# PCB_3U_DAC.net
KiCad netlist of a schematic drawn in Altium Designer
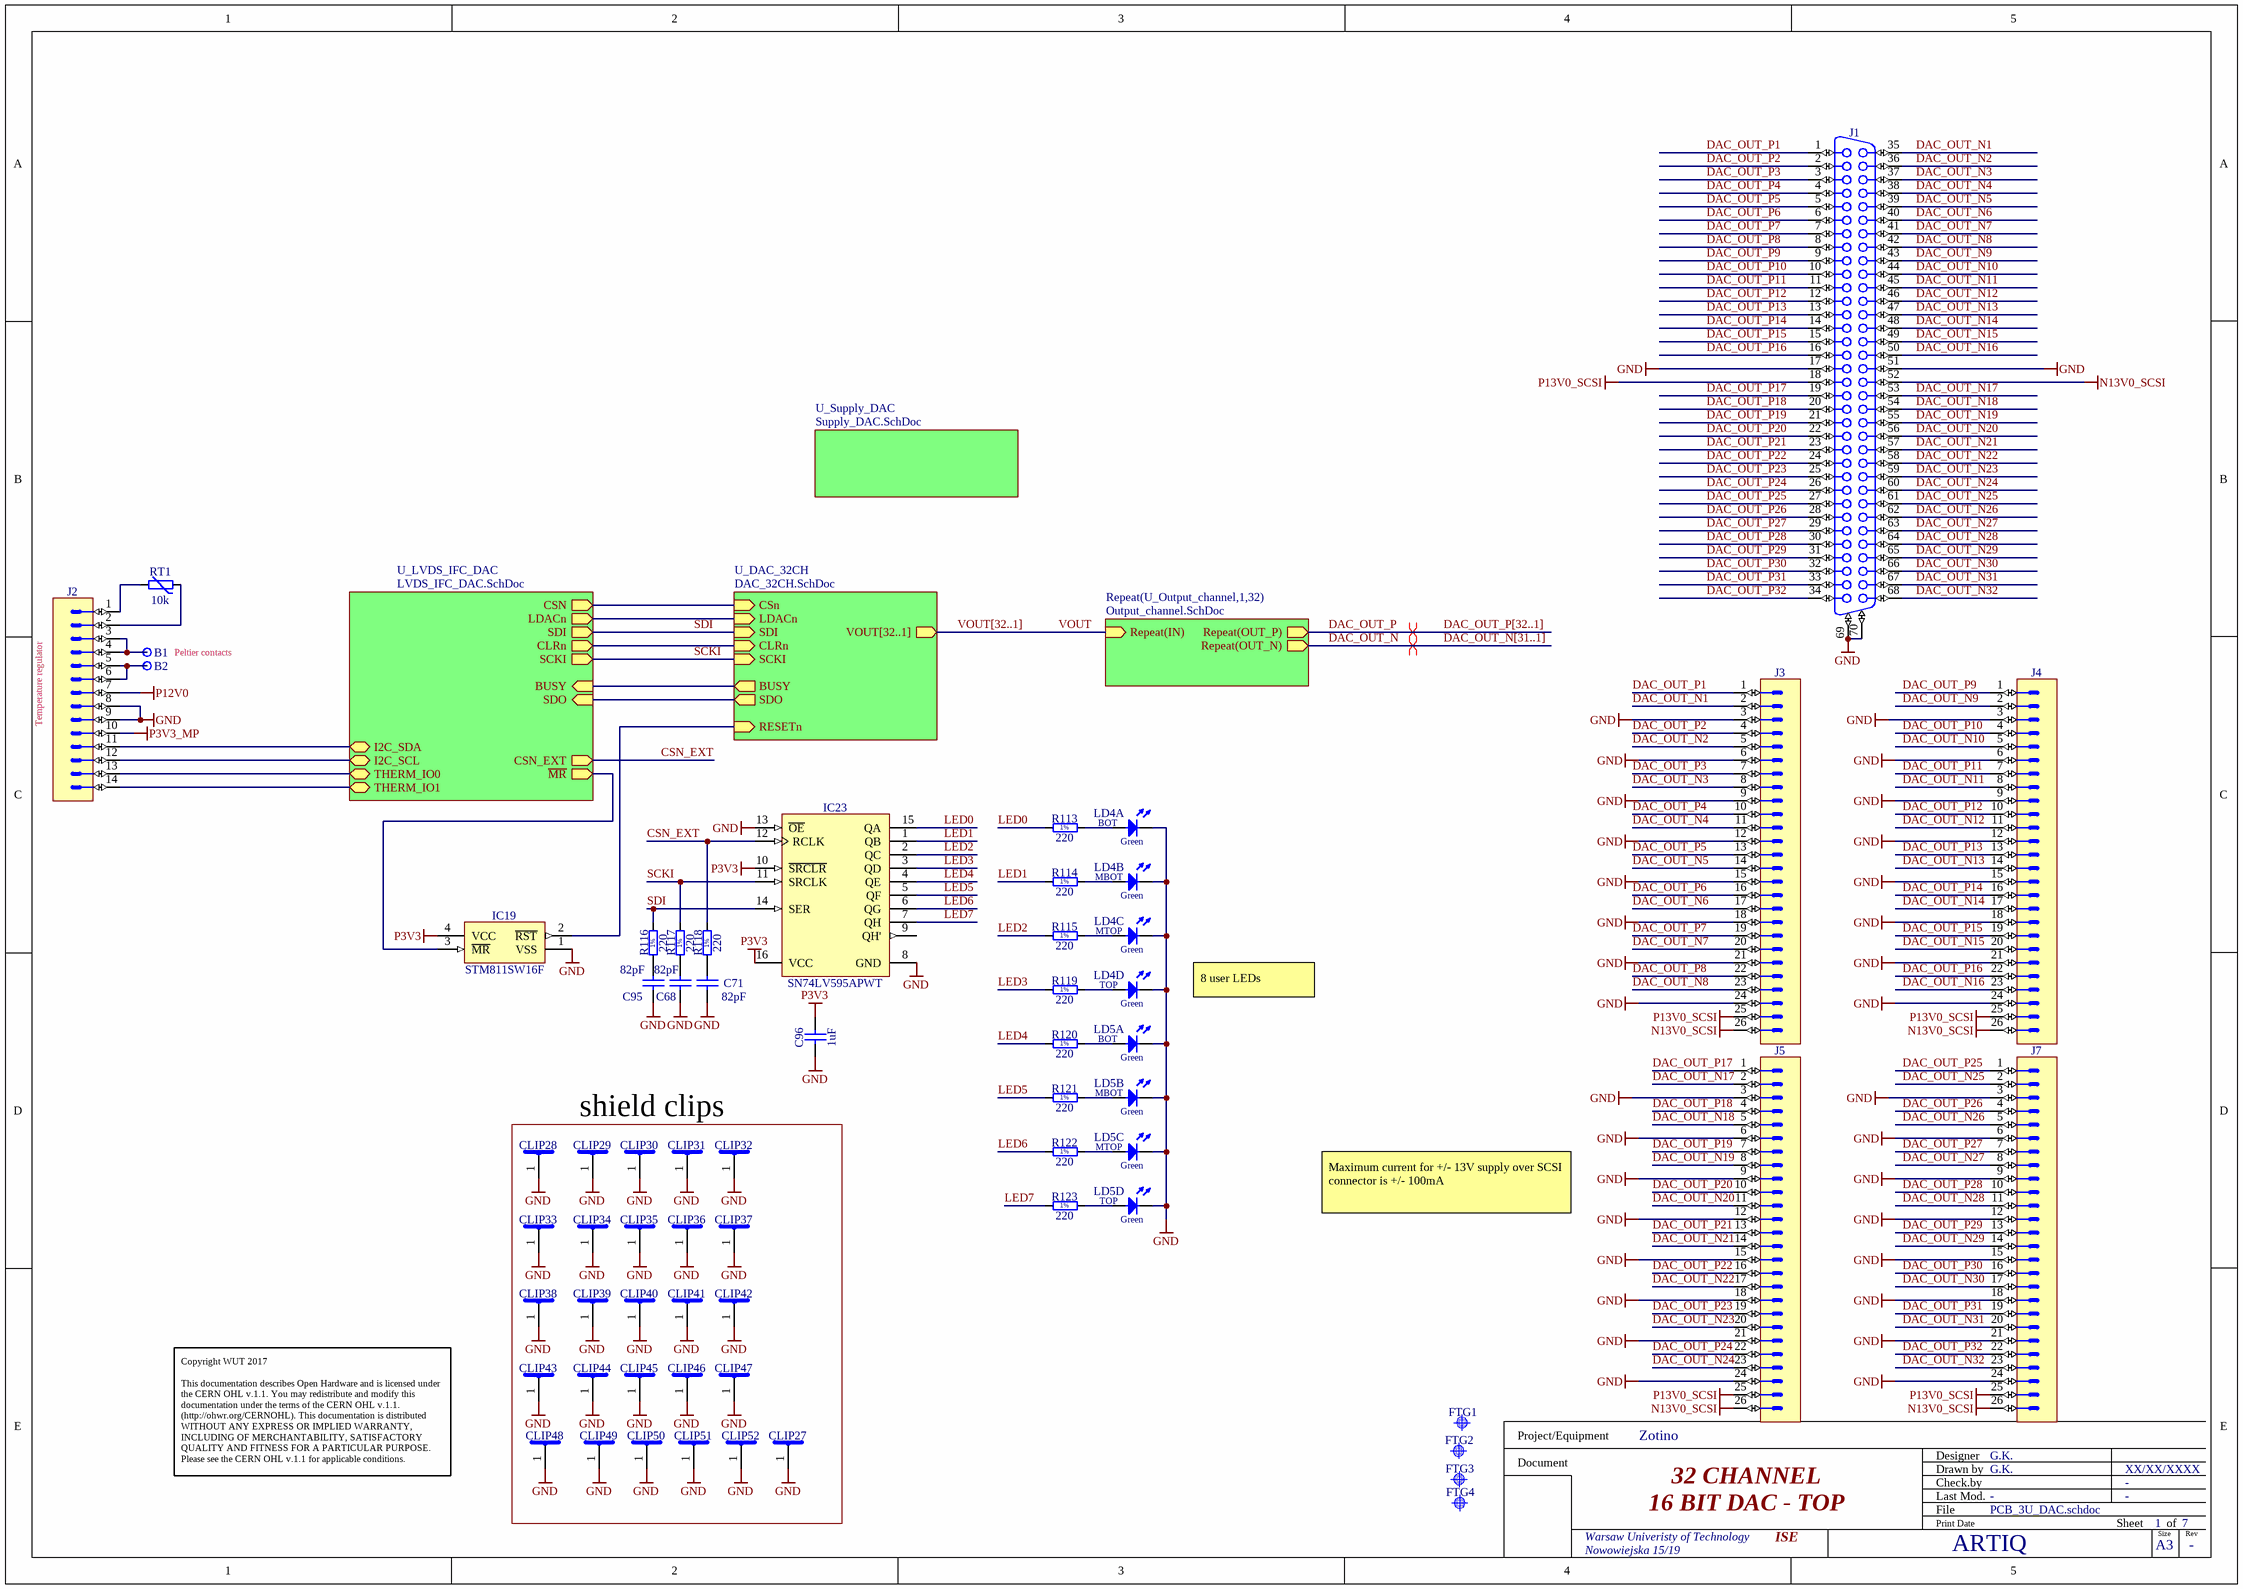
[diagram p0: PCB_3U_DAC.schdoc]

(export (version "E")
  (design (tool "Eeschema 10.0.6"))
  (components
    (comp (ref "B1")
      (value "Plated Hole")
      (footprint "c140h90")
      (description "Single Terminal Socket")
      (fields (field (name "PART NUMBER") "PLATED_HOLE0.9_PAD1.4") (field (name "AUTHOR") "CERN DEM JLC"))
      (libsource (lib "Eletro-mechanical") (part "Single Terminal Socket"))
    )
    (comp (ref "B2")
      (value "Plated Hole")
      (footprint "c140h90")
      (description "Single Terminal Socket")
      (fields (field (name "PART NUMBER") "PLATED_HOLE0.9_PAD1.4") (field (name "AUTHOR") "CERN DEM JLC"))
      (libsource (lib "Eletro-mechanical") (part "Single Terminal Socket"))
    )
    (comp (ref "C68")
      (value "82pF")
      (footprint "CAPC1608X87N")
      (description "Non-polarised capacitor")
      (fields
        (field (name "PART NUMBER") "CC0603_82PF_50V_5%_NP0")
        (field (name "VOLTAGE") "50V")
        (field (name "AUTHOR") "CERN DEM JLC")
      )
      (libsource (lib "Capacitors") (part "Capacitor - non polarized"))
    )
    (comp (ref "C71")
      (value "82pF")
      (footprint "CAPC1608X87N")
      (description "Non-polarised capacitor")
      (fields
        (field (name "PART NUMBER") "CC0603_82PF_50V_5%_NP0")
        (field (name "VOLTAGE") "50V")
        (field (name "AUTHOR") "CERN DEM JLC")
      )
      (libsource (lib "Capacitors") (part "Capacitor - non polarized"))
    )
    (comp (ref "C95")
      (value "82pF")
      (footprint "CAPC1608X87N")
      (description "Non-polarised capacitor")
      (fields
        (field (name "PART NUMBER") "CC0603_82PF_50V_5%_NP0")
        (field (name "VOLTAGE") "50V")
        (field (name "AUTHOR") "CERN DEM JLC")
      )
      (libsource (lib "Capacitors") (part "Capacitor - non polarized"))
    )
    (comp (ref "C96")
      (value "1uF")
      (footprint "CAPC1608X87N")
      (description "Non-polarised capacitor")
      (fields
        (field (name "PART NUMBER") "CC0603_1UF_25V_10%_X7R")
        (field (name "VOLTAGE") "25V")
        (field (name "AUTHOR") "CERN DEM JLC")
      )
      (libsource (lib "Capacitors") (part "Capacitor - non polarized"))
    )
    (comp (ref "CLIP27")
      (value "S1411-46R")
      (footprint "CLIP_HOLLAND-SHIELDING_LC")
      (description "Surface Mount Clip for PCB Screening Covers")
      (fields (field (name "MANUFACTURER") "HARWIN") (field (name "AUTHOR") "CERN DEM JLC"))
      (libsource (lib "LIBRARY_SCH") (part "SHIELD_CLIP"))
    )
    (comp (ref "CLIP28")
      (value "S1411-46R")
      (footprint "CLIP_HOLLAND-SHIELDING_LC")
      (description "Surface Mount Clip for PCB Screening Covers")
      (fields (field (name "MANUFACTURER") "HARWIN") (field (name "AUTHOR") "CERN DEM JLC"))
      (libsource (lib "LIBRARY_SCH") (part "SHIELD_CLIP"))
    )
    (comp (ref "CLIP29")
      (value "S1411-46R")
      (footprint "CLIP_HOLLAND-SHIELDING_LC")
      (description "Surface Mount Clip for PCB Screening Covers")
      (fields (field (name "MANUFACTURER") "HARWIN") (field (name "AUTHOR") "CERN DEM JLC"))
      (libsource (lib "LIBRARY_SCH") (part "SHIELD_CLIP"))
    )
    (comp (ref "CLIP30")
      (value "S1411-46R")
      (footprint "CLIP_HOLLAND-SHIELDING_LC")
      (description "Surface Mount Clip for PCB Screening Covers")
      (fields (field (name "MANUFACTURER") "HARWIN") (field (name "AUTHOR") "CERN DEM JLC"))
      (libsource (lib "LIBRARY_SCH") (part "SHIELD_CLIP"))
    )
    (comp (ref "CLIP31")
      (value "S1411-46R")
      (footprint "CLIP_HOLLAND-SHIELDING_LC")
      (description "Surface Mount Clip for PCB Screening Covers")
      (fields (field (name "MANUFACTURER") "HARWIN") (field (name "AUTHOR") "CERN DEM JLC"))
      (libsource (lib "LIBRARY_SCH") (part "SHIELD_CLIP"))
    )
    (comp (ref "CLIP32")
      (value "S1411-46R")
      (footprint "CLIP_HOLLAND-SHIELDING_LC")
      (description "Surface Mount Clip for PCB Screening Covers")
      (fields (field (name "MANUFACTURER") "HARWIN") (field (name "AUTHOR") "CERN DEM JLC"))
      (libsource (lib "LIBRARY_SCH") (part "SHIELD_CLIP"))
    )
    (comp (ref "CLIP33")
      (value "S1411-46R")
      (footprint "CLIP_HOLLAND-SHIELDING_LC")
      (description "Surface Mount Clip for PCB Screening Covers")
      (fields (field (name "MANUFACTURER") "HARWIN") (field (name "AUTHOR") "CERN DEM JLC"))
      (libsource (lib "LIBRARY_SCH") (part "SHIELD_CLIP"))
    )
    (comp (ref "CLIP34")
      (value "S1411-46R")
      (footprint "CLIP_HOLLAND-SHIELDING_LC")
      (description "Surface Mount Clip for PCB Screening Covers")
      (fields (field (name "MANUFACTURER") "HARWIN") (field (name "AUTHOR") "CERN DEM JLC"))
      (libsource (lib "LIBRARY_SCH") (part "SHIELD_CLIP"))
    )
    (comp (ref "CLIP35")
      (value "S1411-46R")
      (footprint "CLIP_HOLLAND-SHIELDING_LC")
      (description "Surface Mount Clip for PCB Screening Covers")
      (fields (field (name "MANUFACTURER") "HARWIN") (field (name "AUTHOR") "CERN DEM JLC"))
      (libsource (lib "LIBRARY_SCH") (part "SHIELD_CLIP"))
    )
    (comp (ref "CLIP36")
      (value "S1411-46R")
      (footprint "CLIP_HOLLAND-SHIELDING_LC")
      (description "Surface Mount Clip for PCB Screening Covers")
      (fields (field (name "MANUFACTURER") "HARWIN") (field (name "AUTHOR") "CERN DEM JLC"))
      (libsource (lib "LIBRARY_SCH") (part "SHIELD_CLIP"))
    )
    (comp (ref "CLIP37")
      (value "S1411-46R")
      (footprint "CLIP_HOLLAND-SHIELDING_LC")
      (description "Surface Mount Clip for PCB Screening Covers")
      (fields (field (name "MANUFACTURER") "HARWIN") (field (name "AUTHOR") "CERN DEM JLC"))
      (libsource (lib "LIBRARY_SCH") (part "SHIELD_CLIP"))
    )
    (comp (ref "CLIP38")
      (value "S1411-46R")
      (footprint "CLIP_HOLLAND-SHIELDING_LC")
      (description "Surface Mount Clip for PCB Screening Covers")
      (fields (field (name "MANUFACTURER") "HARWIN") (field (name "AUTHOR") "CERN DEM JLC"))
      (libsource (lib "LIBRARY_SCH") (part "SHIELD_CLIP"))
    )
    (comp (ref "CLIP39")
      (value "S1411-46R")
      (footprint "CLIP_HOLLAND-SHIELDING_LC")
      (description "Surface Mount Clip for PCB Screening Covers")
      (fields (field (name "MANUFACTURER") "HARWIN") (field (name "AUTHOR") "CERN DEM JLC"))
      (libsource (lib "LIBRARY_SCH") (part "SHIELD_CLIP"))
    )
    (comp (ref "CLIP40")
      (value "S1411-46R")
      (footprint "CLIP_HOLLAND-SHIELDING_LC")
      (description "Surface Mount Clip for PCB Screening Covers")
      (fields (field (name "MANUFACTURER") "HARWIN") (field (name "AUTHOR") "CERN DEM JLC"))
      (libsource (lib "LIBRARY_SCH") (part "SHIELD_CLIP"))
    )
    (comp (ref "CLIP41")
      (value "S1411-46R")
      (footprint "CLIP_HOLLAND-SHIELDING_LC")
      (description "Surface Mount Clip for PCB Screening Covers")
      (fields (field (name "MANUFACTURER") "HARWIN") (field (name "AUTHOR") "CERN DEM JLC"))
      (libsource (lib "LIBRARY_SCH") (part "SHIELD_CLIP"))
    )
    (comp (ref "CLIP42")
      (value "S1411-46R")
      (footprint "CLIP_HOLLAND-SHIELDING_LC")
      (description "Surface Mount Clip for PCB Screening Covers")
      (fields (field (name "MANUFACTURER") "HARWIN") (field (name "AUTHOR") "CERN DEM JLC"))
      (libsource (lib "LIBRARY_SCH") (part "SHIELD_CLIP"))
    )
    (comp (ref "CLIP43")
      (value "S1411-46R")
      (footprint "CLIP_HOLLAND-SHIELDING_LC")
      (description "Surface Mount Clip for PCB Screening Covers")
      (fields (field (name "MANUFACTURER") "HARWIN") (field (name "AUTHOR") "CERN DEM JLC"))
      (libsource (lib "LIBRARY_SCH") (part "SHIELD_CLIP"))
    )
    (comp (ref "CLIP44")
      (value "S1411-46R")
      (footprint "CLIP_HOLLAND-SHIELDING_LC")
      (description "Surface Mount Clip for PCB Screening Covers")
      (fields (field (name "MANUFACTURER") "HARWIN") (field (name "AUTHOR") "CERN DEM JLC"))
      (libsource (lib "LIBRARY_SCH") (part "SHIELD_CLIP"))
    )
    (comp (ref "CLIP45")
      (value "S1411-46R")
      (footprint "CLIP_HOLLAND-SHIELDING_LC")
      (description "Surface Mount Clip for PCB Screening Covers")
      (fields (field (name "MANUFACTURER") "HARWIN") (field (name "AUTHOR") "CERN DEM JLC"))
      (libsource (lib "LIBRARY_SCH") (part "SHIELD_CLIP"))
    )
    (comp (ref "CLIP46")
      (value "S1411-46R")
      (footprint "CLIP_HOLLAND-SHIELDING_LC")
      (description "Surface Mount Clip for PCB Screening Covers")
      (fields (field (name "MANUFACTURER") "HARWIN") (field (name "AUTHOR") "CERN DEM JLC"))
      (libsource (lib "LIBRARY_SCH") (part "SHIELD_CLIP"))
    )
    (comp (ref "CLIP47")
      (value "S1411-46R")
      (footprint "CLIP_HOLLAND-SHIELDING_LC")
      (description "Surface Mount Clip for PCB Screening Covers")
      (fields (field (name "MANUFACTURER") "HARWIN") (field (name "AUTHOR") "CERN DEM JLC"))
      (libsource (lib "LIBRARY_SCH") (part "SHIELD_CLIP"))
    )
    (comp (ref "CLIP48")
      (value "S1411-46R")
      (footprint "CLIP_HOLLAND-SHIELDING_LC")
      (description "Surface Mount Clip for PCB Screening Covers")
      (fields (field (name "MANUFACTURER") "HARWIN") (field (name "AUTHOR") "CERN DEM JLC"))
      (libsource (lib "LIBRARY_SCH") (part "SHIELD_CLIP"))
    )
    (comp (ref "CLIP49")
      (value "S1411-46R")
      (footprint "CLIP_HOLLAND-SHIELDING_LC")
      (description "Surface Mount Clip for PCB Screening Covers")
      (fields (field (name "MANUFACTURER") "HARWIN") (field (name "AUTHOR") "CERN DEM JLC"))
      (libsource (lib "LIBRARY_SCH") (part "SHIELD_CLIP"))
    )
    (comp (ref "CLIP50")
      (value "S1411-46R")
      (footprint "CLIP_HOLLAND-SHIELDING_LC")
      (description "Surface Mount Clip for PCB Screening Covers")
      (fields (field (name "MANUFACTURER") "HARWIN") (field (name "AUTHOR") "CERN DEM JLC"))
      (libsource (lib "LIBRARY_SCH") (part "SHIELD_CLIP"))
    )
    (comp (ref "CLIP51")
      (value "S1411-46R")
      (footprint "CLIP_HOLLAND-SHIELDING_LC")
      (description "Surface Mount Clip for PCB Screening Covers")
      (fields (field (name "MANUFACTURER") "HARWIN") (field (name "AUTHOR") "CERN DEM JLC"))
      (libsource (lib "LIBRARY_SCH") (part "SHIELD_CLIP"))
    )
    (comp (ref "CLIP52")
      (value "S1411-46R")
      (footprint "CLIP_HOLLAND-SHIELDING_LC")
      (description "Surface Mount Clip for PCB Screening Covers")
      (fields (field (name "MANUFACTURER") "HARWIN") (field (name "AUTHOR") "CERN DEM JLC"))
      (libsource (lib "LIBRARY_SCH") (part "SHIELD_CLIP"))
    )
    (comp (ref "FTG1")
      (value "Use only in PCB")
      (footprint "FIDUCIAL_TOP_C100-200")
      (description "Fiducial Target")
      (fields (field (name "PART NUMBER") "FIDUCIAL_TARGET_C100-200") (field (name "AUTHOR") "CERN DEM JLC"))
      (libsource (lib "Eletro-mechanical") (part "Fiducial Target"))
    )
    (comp (ref "FTG2")
      (value "Use only in PCB")
      (footprint "FIDUCIAL_TOP_S100-200")
      (description "Fiducial Target")
      (fields (field (name "PART NUMBER") "FIDUCIAL_TARGET_S100-200") (field (name "AUTHOR") "CERN DEM JLC"))
      (libsource (lib "Eletro-mechanical") (part "Fiducial Target"))
    )
    (comp (ref "FTG3")
      (value "Use only in PCB")
      (footprint "FIDUCIAL_TOP_S200-400")
      (description "Fiducial Target")
      (fields (field (name "PART NUMBER") "FIDUCIAL_TARGET_S200-400") (field (name "AUTHOR") "CERN DEM JLC"))
      (libsource (lib "Eletro-mechanical") (part "Fiducial Target"))
    )
    (comp (ref "FTG4")
      (value "Use only in PCB")
      (footprint "FIDUCIAL_TOP_S100-200")
      (description "Fiducial Target")
      (fields (field (name "PART NUMBER") "FIDUCIAL_TARGET_S100-200") (field (name "AUTHOR") "CERN DEM JLC"))
      (libsource (lib "Eletro-mechanical") (part "Fiducial Target"))
    )
    (comp (ref "IC19")
      (value "STM811SW16F")
      (footprint "SOT143N")
      (description "Microprocessor Reset Circuit")
      (fields (field (name "MANUFACTURER") "ST MICROELECTRONICS") (field (name "AUTHOR") "CERN DEM JLC"))
      (libsource (lib "ICs And Semiconductors") (part "STM811"))
    )
    (comp (ref "IC23")
      (value "SN74LV595APWT")
      (footprint "SOP65P640X120-16N")
      (description "8-Bit Shift Register With 3-State Output Register")
      (fields (field (name "MANUFACTURER") "TEXAS INSTRUMENTS") (field (name "AUTHOR") "CERN DEM JLC"))
      (libsource (lib "ICs And Semiconductors") (part "74595"))
    )
    (comp (ref "J1")
      (value "D-SUB")
      (footprint "TYCO_5787082-7")
      (description "68 contacts, AMPLIMITE .050\", Right Angled Receptacle Series III")
      (fields
        (field (name "PART NUMBER") "TYCO_5787082-7")
        (field (name "MANUFACTURER") "TYCO ELECTRONICS")
        (field (name "AUTHOR") "CERN DEM JLC")
      )
      (libsource (lib "Connectors") (part "TYCO_5787082-7"))
    )
    (comp (ref "J2")
      (value "Header 14")
      (footprint "3M_N2514-6002RB")
      (description "Connector 14 Male")
      (fields
        (field (name "PART NUMBER") "3M_N2514-6002RB")
        (field (name "MANUFACTURER") "3M")
        (field (name "AUTHOR") "CERN DEM JLC")
      )
      (libsource (lib "Connectors") (part "Connector 14 Male"))
    )
    (comp (ref "J3")
      (value "Header 26")
      (footprint "3M_N2526-6002RB")
      (description "Connector 26 Male")
      (fields
        (field (name "PART NUMBER") "3M_N2526-6002RB")
        (field (name "MANUFACTURER") "3M")
        (field (name "AUTHOR") "CERN DEM JLC")
      )
      (libsource (lib "Connectors") (part "Connector 26 Male"))
    )
    (comp (ref "J4")
      (value "Header 26")
      (footprint "3M_N2526-6002RB")
      (description "Connector 26 Male")
      (fields
        (field (name "PART NUMBER") "3M_N2526-6002RB")
        (field (name "MANUFACTURER") "3M")
        (field (name "AUTHOR") "CERN DEM JLC")
      )
      (libsource (lib "Connectors") (part "Connector 26 Male"))
    )
    (comp (ref "J5")
      (value "Header 26")
      (footprint "3M_N2526-6002RB")
      (description "Connector 26 Male")
      (fields
        (field (name "PART NUMBER") "3M_N2526-6002RB")
        (field (name "MANUFACTURER") "3M")
        (field (name "AUTHOR") "CERN DEM JLC")
      )
      (libsource (lib "Connectors") (part "Connector 26 Male"))
    )
    (comp (ref "J7")
      (value "Header 26")
      (footprint "3M_N2526-6002RB")
      (description "Connector 26 Male")
      (fields
        (field (name "PART NUMBER") "3M_N2526-6002RB")
        (field (name "MANUFACTURER") "3M")
        (field (name "AUTHOR") "CERN DEM JLC")
      )
      (libsource (lib "Connectors") (part "Connector 26 Male"))
    )
    (comp (ref "LD4")
      (value "Green")
      (footprint "LED_BIVAR_H485CGDL")
      (description "LED x4 Green 1C2A-BOT_3C4A_5C6A_7C8A-TOP")
      (fields
        (field (name "PART NUMBER") "LED_BIVAR_H485CGDL")
        (field (name "MANUFACTURER") "BIVAR")
        (field (name "AUTHOR") "CERN DEM JLC")
      )
      (libsource (lib "ICs And Semiconductors") (part "LED x4 Green 1C2A-BOT_3C4A_5C6A_7C8A-TOP"))
    )
    (comp (ref "LD5")
      (value "Green")
      (footprint "LED_BIVAR_H485CGDL")
      (description "LED x4 Green 1C2A-BOT_3C4A_5C6A_7C8A-TOP")
      (fields
        (field (name "PART NUMBER") "LED_BIVAR_H485CGDL")
        (field (name "MANUFACTURER") "BIVAR")
        (field (name "AUTHOR") "CERN DEM JLC")
      )
      (libsource (lib "ICs And Semiconductors") (part "LED x4 Green 1C2A-BOT_3C4A_5C6A_7C8A-TOP"))
    )
    (comp (ref "R113")
      (value "220")
      (footprint "RESC1608X55N")
      (description "Resistor - 1%")
      (fields
        (field (name "PART NUMBER") "R0603_220R_1%_0.1W_100PPM")
        (field (name "POWER") "0.1W")
        (field (name "AUTHOR") "CERN DEM JLC")
      )
      (libsource (lib "Resistors") (part "Resistor - 1%"))
    )
    (comp (ref "R114")
      (value "220")
      (footprint "RESC1608X55N")
      (description "Resistor - 1%")
      (fields
        (field (name "PART NUMBER") "R0603_220R_1%_0.1W_100PPM")
        (field (name "POWER") "0.1W")
        (field (name "AUTHOR") "CERN DEM JLC")
      )
      (libsource (lib "Resistors") (part "Resistor - 1%"))
    )
    (comp (ref "R115")
      (value "220")
      (footprint "RESC1608X55N")
      (description "Resistor - 1%")
      (fields
        (field (name "PART NUMBER") "R0603_220R_1%_0.1W_100PPM")
        (field (name "POWER") "0.1W")
        (field (name "AUTHOR") "CERN DEM JLC")
      )
      (libsource (lib "Resistors") (part "Resistor - 1%"))
    )
    (comp (ref "R116")
      (value "220")
      (footprint "RESC1608X55N")
      (description "Resistor - 1%")
      (fields
        (field (name "PART NUMBER") "R0603_220R_1%_0.1W_100PPM")
        (field (name "POWER") "0.1W")
        (field (name "AUTHOR") "CERN DEM JLC")
      )
      (libsource (lib "Resistors") (part "Resistor - 1%"))
    )
    (comp (ref "R117")
      (value "220")
      (footprint "RESC1608X55N")
      (description "Resistor - 1%")
      (fields
        (field (name "PART NUMBER") "R0603_220R_1%_0.1W_100PPM")
        (field (name "POWER") "0.1W")
        (field (name "AUTHOR") "CERN DEM JLC")
      )
      (libsource (lib "Resistors") (part "Resistor - 1%"))
    )
    (comp (ref "R118")
      (value "220")
      (footprint "RESC1608X55N")
      (description "Resistor - 1%")
      (fields
        (field (name "PART NUMBER") "R0603_220R_1%_0.1W_100PPM")
        (field (name "POWER") "0.1W")
        (field (name "AUTHOR") "CERN DEM JLC")
      )
      (libsource (lib "Resistors") (part "Resistor - 1%"))
    )
    (comp (ref "R119")
      (value "220")
      (footprint "RESC1608X55N")
      (description "Resistor - 1%")
      (fields
        (field (name "PART NUMBER") "R0603_220R_1%_0.1W_100PPM")
        (field (name "POWER") "0.1W")
        (field (name "AUTHOR") "CERN DEM JLC")
      )
      (libsource (lib "Resistors") (part "Resistor - 1%"))
    )
    (comp (ref "R120")
      (value "220")
      (footprint "RESC1608X55N")
      (description "Resistor - 1%")
      (fields
        (field (name "PART NUMBER") "R0603_220R_1%_0.1W_100PPM")
        (field (name "POWER") "0.1W")
        (field (name "AUTHOR") "CERN DEM JLC")
      )
      (libsource (lib "Resistors") (part "Resistor - 1%"))
    )
    (comp (ref "R121")
      (value "220")
      (footprint "RESC1608X55N")
      (description "Resistor - 1%")
      (fields
        (field (name "PART NUMBER") "R0603_220R_1%_0.1W_100PPM")
        (field (name "POWER") "0.1W")
        (field (name "AUTHOR") "CERN DEM JLC")
      )
      (libsource (lib "Resistors") (part "Resistor - 1%"))
    )
    (comp (ref "R122")
      (value "220")
      (footprint "RESC1608X55N")
      (description "Resistor - 1%")
      (fields
        (field (name "PART NUMBER") "R0603_220R_1%_0.1W_100PPM")
        (field (name "POWER") "0.1W")
        (field (name "AUTHOR") "CERN DEM JLC")
      )
      (libsource (lib "Resistors") (part "Resistor - 1%"))
    )
    (comp (ref "R123")
      (value "220")
      (footprint "RESC1608X55N")
      (description "Resistor - 1%")
      (fields
        (field (name "PART NUMBER") "R0603_220R_1%_0.1W_100PPM")
        (field (name "POWER") "0.1W")
        (field (name "AUTHOR") "CERN DEM JLC")
      )
      (libsource (lib "Resistors") (part "Resistor - 1%"))
    )
    (comp (ref "RT1")
      (value "10k")
      (footprint "THERMC1608X90N")
      (description "Thermistor NTC (Negative Temperature Coefficient)")
      (fields
        (field (name "PART NUMBER") "THERM_NTC_10K_EPCOS_B57330V2103J260")
        (field (name "POWER") "180mW")
        (field (name "AUTHOR") "CERN DEM BC")
      )
      (libsource (lib "Resistors") (part "Thermistor NTC"))
    )
  )
  (nets
    (net (code "36") (name "/CSN_EXT") (class "Default")
      (node (ref "IC23") (pin "12") (pinfunction "RCLK_12") (pintype "input"))
      (node (ref "R118") (pin "2") (pinfunction "2_2") (pintype "passive"))
    )
    (net (code "38") (name "/DAC_OUT_N1") (class "Default")
      (node (ref "J1") (pin "35") (pinfunction "35_35") (pintype "bidirectional"))
      (node (ref "J3") (pin "2") (pinfunction "2_2") (pintype "bidirectional"))
    )
    (net (code "39") (name "/DAC_OUT_N2") (class "Default")
      (node (ref "J1") (pin "36") (pinfunction "36_36") (pintype "bidirectional"))
      (node (ref "J3") (pin "5") (pinfunction "5_5") (pintype "bidirectional"))
    )
    (net (code "40") (name "/DAC_OUT_N3") (class "Default")
      (node (ref "J1") (pin "37") (pinfunction "37_37") (pintype "bidirectional"))
      (node (ref "J3") (pin "8") (pinfunction "8_8") (pintype "bidirectional"))
    )
    (net (code "41") (name "/DAC_OUT_N4") (class "Default")
      (node (ref "J1") (pin "38") (pinfunction "38_38") (pintype "bidirectional"))
      (node (ref "J3") (pin "11") (pinfunction "11_11") (pintype "bidirectional"))
    )
    (net (code "42") (name "/DAC_OUT_N5") (class "Default")
      (node (ref "J1") (pin "39") (pinfunction "39_39") (pintype "bidirectional"))
      (node (ref "J3") (pin "14") (pinfunction "14_14") (pintype "bidirectional"))
    )
    (net (code "43") (name "/DAC_OUT_N6") (class "Default")
      (node (ref "J1") (pin "40") (pinfunction "40_40") (pintype "bidirectional"))
      (node (ref "J3") (pin "17") (pinfunction "17_17") (pintype "bidirectional"))
    )
    (net (code "44") (name "/DAC_OUT_N7") (class "Default")
      (node (ref "J1") (pin "41") (pinfunction "41_41") (pintype "bidirectional"))
      (node (ref "J3") (pin "20") (pinfunction "20_20") (pintype "bidirectional"))
    )
    (net (code "45") (name "/DAC_OUT_N8") (class "Default")
      (node (ref "J1") (pin "42") (pinfunction "42_42") (pintype "bidirectional"))
      (node (ref "J3") (pin "23") (pinfunction "23_23") (pintype "bidirectional"))
    )
    (net (code "46") (name "/DAC_OUT_N9") (class "Default")
      (node (ref "J1") (pin "43") (pinfunction "43_43") (pintype "bidirectional"))
      (node (ref "J4") (pin "2") (pinfunction "2_2") (pintype "bidirectional"))
    )
    (net (code "47") (name "/DAC_OUT_N10") (class "Default")
      (node (ref "J1") (pin "44") (pinfunction "44_44") (pintype "bidirectional"))
      (node (ref "J4") (pin "5") (pinfunction "5_5") (pintype "bidirectional"))
    )
    (net (code "48") (name "/DAC_OUT_N11") (class "Default")
      (node (ref "J1") (pin "45") (pinfunction "45_45") (pintype "bidirectional"))
      (node (ref "J4") (pin "8") (pinfunction "8_8") (pintype "bidirectional"))
    )
    (net (code "49") (name "/DAC_OUT_N12") (class "Default")
      (node (ref "J1") (pin "46") (pinfunction "46_46") (pintype "bidirectional"))
      (node (ref "J4") (pin "11") (pinfunction "11_11") (pintype "bidirectional"))
    )
    (net (code "50") (name "/DAC_OUT_N13") (class "Default")
      (node (ref "J1") (pin "47") (pinfunction "47_47") (pintype "bidirectional"))
      (node (ref "J4") (pin "14") (pinfunction "14_14") (pintype "bidirectional"))
    )
    (net (code "51") (name "/DAC_OUT_N14") (class "Default")
      (node (ref "J1") (pin "48") (pinfunction "48_48") (pintype "bidirectional"))
      (node (ref "J4") (pin "17") (pinfunction "17_17") (pintype "bidirectional"))
    )
    (net (code "52") (name "/DAC_OUT_N15") (class "Default")
      (node (ref "J1") (pin "49") (pinfunction "49_49") (pintype "bidirectional"))
      (node (ref "J4") (pin "20") (pinfunction "20_20") (pintype "bidirectional"))
    )
    (net (code "53") (name "/DAC_OUT_N16") (class "Default")
      (node (ref "J1") (pin "50") (pinfunction "50_50") (pintype "bidirectional"))
      (node (ref "J4") (pin "23") (pinfunction "23_23") (pintype "bidirectional"))
    )
    (net (code "54") (name "/DAC_OUT_N17") (class "Default")
      (node (ref "J1") (pin "53") (pinfunction "53_53") (pintype "bidirectional"))
      (node (ref "J5") (pin "2") (pinfunction "2_2") (pintype "bidirectional"))
    )
    (net (code "55") (name "/DAC_OUT_N18") (class "Default")
      (node (ref "J1") (pin "54") (pinfunction "54_54") (pintype "bidirectional"))
      (node (ref "J5") (pin "5") (pinfunction "5_5") (pintype "bidirectional"))
    )
    (net (code "56") (name "/DAC_OUT_N19") (class "Default")
      (node (ref "J1") (pin "55") (pinfunction "55_55") (pintype "bidirectional"))
      (node (ref "J5") (pin "8") (pinfunction "8_8") (pintype "bidirectional"))
    )
    (net (code "57") (name "/DAC_OUT_N20") (class "Default")
      (node (ref "J1") (pin "56") (pinfunction "56_56") (pintype "bidirectional"))
      (node (ref "J5") (pin "11") (pinfunction "11_11") (pintype "bidirectional"))
    )
    (net (code "58") (name "/DAC_OUT_N21") (class "Default")
      (node (ref "J1") (pin "57") (pinfunction "57_57") (pintype "bidirectional"))
      (node (ref "J5") (pin "14") (pinfunction "14_14") (pintype "bidirectional"))
    )
    (net (code "59") (name "/DAC_OUT_N22") (class "Default")
      (node (ref "J1") (pin "58") (pinfunction "58_58") (pintype "bidirectional"))
      (node (ref "J5") (pin "17") (pinfunction "17_17") (pintype "bidirectional"))
    )
    (net (code "60") (name "/DAC_OUT_N23") (class "Default")
      (node (ref "J1") (pin "59") (pinfunction "59_59") (pintype "bidirectional"))
      (node (ref "J5") (pin "20") (pinfunction "20_20") (pintype "bidirectional"))
    )
    (net (code "61") (name "/DAC_OUT_N24") (class "Default")
      (node (ref "J1") (pin "60") (pinfunction "60_60") (pintype "bidirectional"))
      (node (ref "J5") (pin "23") (pinfunction "23_23") (pintype "bidirectional"))
    )
    (net (code "62") (name "/DAC_OUT_N25") (class "Default")
      (node (ref "J1") (pin "61") (pinfunction "61_61") (pintype "bidirectional"))
      (node (ref "J7") (pin "2") (pinfunction "2_2") (pintype "bidirectional"))
    )
    (net (code "63") (name "/DAC_OUT_N26") (class "Default")
      (node (ref "J1") (pin "62") (pinfunction "62_62") (pintype "bidirectional"))
      (node (ref "J7") (pin "5") (pinfunction "5_5") (pintype "bidirectional"))
    )
    (net (code "64") (name "/DAC_OUT_N27") (class "Default")
      (node (ref "J1") (pin "63") (pinfunction "63_63") (pintype "bidirectional"))
      (node (ref "J7") (pin "8") (pinfunction "8_8") (pintype "bidirectional"))
    )
    (net (code "65") (name "/DAC_OUT_N28") (class "Default")
      (node (ref "J1") (pin "64") (pinfunction "64_64") (pintype "bidirectional"))
      (node (ref "J7") (pin "11") (pinfunction "11_11") (pintype "bidirectional"))
    )
    (net (code "66") (name "/DAC_OUT_N29") (class "Default")
      (node (ref "J1") (pin "65") (pinfunction "65_65") (pintype "bidirectional"))
      (node (ref "J7") (pin "14") (pinfunction "14_14") (pintype "bidirectional"))
    )
    (net (code "67") (name "/DAC_OUT_N30") (class "Default")
      (node (ref "J1") (pin "66") (pinfunction "66_66") (pintype "bidirectional"))
      (node (ref "J7") (pin "17") (pinfunction "17_17") (pintype "bidirectional"))
    )
    (net (code "68") (name "/DAC_OUT_N31") (class "Default")
      (node (ref "J1") (pin "67") (pinfunction "67_67") (pintype "bidirectional"))
      (node (ref "J7") (pin "20") (pinfunction "20_20") (pintype "bidirectional"))
    )
    (net (code "69") (name "/DAC_OUT_N32") (class "Default")
      (node (ref "J1") (pin "68") (pinfunction "68_68") (pintype "bidirectional"))
      (node (ref "J7") (pin "23") (pinfunction "23_23") (pintype "bidirectional"))
    )
    (net (code "72") (name "/DAC_OUT_P1") (class "Default")
      (node (ref "J1") (pin "1") (pinfunction "1_1") (pintype "bidirectional"))
      (node (ref "J3") (pin "1") (pinfunction "1_1") (pintype "bidirectional"))
    )
    (net (code "73") (name "/DAC_OUT_P2") (class "Default")
      (node (ref "J1") (pin "2") (pinfunction "2_2") (pintype "bidirectional"))
      (node (ref "J3") (pin "4") (pinfunction "4_4") (pintype "bidirectional"))
    )
    (net (code "74") (name "/DAC_OUT_P3") (class "Default")
      (node (ref "J1") (pin "3") (pinfunction "3_3") (pintype "bidirectional"))
      (node (ref "J3") (pin "7") (pinfunction "7_7") (pintype "bidirectional"))
    )
    (net (code "75") (name "/DAC_OUT_P4") (class "Default")
      (node (ref "J1") (pin "4") (pinfunction "4_4") (pintype "bidirectional"))
      (node (ref "J3") (pin "10") (pinfunction "10_10") (pintype "bidirectional"))
    )
    (net (code "76") (name "/DAC_OUT_P5") (class "Default")
      (node (ref "J1") (pin "5") (pinfunction "5_5") (pintype "bidirectional"))
      (node (ref "J3") (pin "13") (pinfunction "13_13") (pintype "bidirectional"))
    )
    (net (code "77") (name "/DAC_OUT_P6") (class "Default")
      (node (ref "J1") (pin "6") (pinfunction "6_6") (pintype "bidirectional"))
      (node (ref "J3") (pin "16") (pinfunction "16_16") (pintype "bidirectional"))
    )
    (net (code "78") (name "/DAC_OUT_P7") (class "Default")
      (node (ref "J1") (pin "7") (pinfunction "7_7") (pintype "bidirectional"))
      (node (ref "J3") (pin "19") (pinfunction "19_19") (pintype "bidirectional"))
    )
    (net (code "79") (name "/DAC_OUT_P8") (class "Default")
      (node (ref "J1") (pin "8") (pinfunction "8_8") (pintype "bidirectional"))
      (node (ref "J3") (pin "22") (pinfunction "22_22") (pintype "bidirectional"))
    )
    (net (code "80") (name "/DAC_OUT_P9") (class "Default")
      (node (ref "J1") (pin "9") (pinfunction "9_9") (pintype "bidirectional"))
      (node (ref "J4") (pin "1") (pinfunction "1_1") (pintype "bidirectional"))
    )
    (net (code "81") (name "/DAC_OUT_P10") (class "Default")
      (node (ref "J1") (pin "10") (pinfunction "10_10") (pintype "bidirectional"))
      (node (ref "J4") (pin "4") (pinfunction "4_4") (pintype "bidirectional"))
    )
    (net (code "82") (name "/DAC_OUT_P11") (class "Default")
      (node (ref "J1") (pin "11") (pinfunction "11_11") (pintype "bidirectional"))
      (node (ref "J4") (pin "7") (pinfunction "7_7") (pintype "bidirectional"))
    )
    (net (code "83") (name "/DAC_OUT_P12") (class "Default")
      (node (ref "J1") (pin "12") (pinfunction "12_12") (pintype "bidirectional"))
      (node (ref "J4") (pin "10") (pinfunction "10_10") (pintype "bidirectional"))
    )
    (net (code "84") (name "/DAC_OUT_P13") (class "Default")
      (node (ref "J1") (pin "13") (pinfunction "13_13") (pintype "bidirectional"))
      (node (ref "J4") (pin "13") (pinfunction "13_13") (pintype "bidirectional"))
    )
    (net (code "85") (name "/DAC_OUT_P14") (class "Default")
      (node (ref "J1") (pin "14") (pinfunction "14_14") (pintype "bidirectional"))
      (node (ref "J4") (pin "16") (pinfunction "16_16") (pintype "bidirectional"))
    )
    (net (code "86") (name "/DAC_OUT_P15") (class "Default")
      (node (ref "J1") (pin "15") (pinfunction "15_15") (pintype "bidirectional"))
      (node (ref "J4") (pin "19") (pinfunction "19_19") (pintype "bidirectional"))
    )
    (net (code "87") (name "/DAC_OUT_P16") (class "Default")
      (node (ref "J1") (pin "16") (pinfunction "16_16") (pintype "bidirectional"))
      (node (ref "J4") (pin "22") (pinfunction "22_22") (pintype "bidirectional"))
    )
    (net (code "88") (name "/DAC_OUT_P17") (class "Default")
      (node (ref "J1") (pin "19") (pinfunction "19_19") (pintype "bidirectional"))
      (node (ref "J5") (pin "1") (pinfunction "1_1") (pintype "bidirectional"))
    )
    (net (code "89") (name "/DAC_OUT_P18") (class "Default")
      (node (ref "J1") (pin "20") (pinfunction "20_20") (pintype "bidirectional"))
      (node (ref "J5") (pin "4") (pinfunction "4_4") (pintype "bidirectional"))
    )
    (net (code "90") (name "/DAC_OUT_P19") (class "Default")
      (node (ref "J1") (pin "21") (pinfunction "21_21") (pintype "bidirectional"))
      (node (ref "J5") (pin "7") (pinfunction "7_7") (pintype "bidirectional"))
    )
    (net (code "91") (name "/DAC_OUT_P20") (class "Default")
      (node (ref "J1") (pin "22") (pinfunction "22_22") (pintype "bidirectional"))
      (node (ref "J5") (pin "10") (pinfunction "10_10") (pintype "bidirectional"))
    )
    (net (code "92") (name "/DAC_OUT_P21") (class "Default")
      (node (ref "J1") (pin "23") (pinfunction "23_23") (pintype "bidirectional"))
      (node (ref "J5") (pin "13") (pinfunction "13_13") (pintype "bidirectional"))
    )
    (net (code "93") (name "/DAC_OUT_P22") (class "Default")
      (node (ref "J1") (pin "24") (pinfunction "24_24") (pintype "bidirectional"))
      (node (ref "J5") (pin "16") (pinfunction "16_16") (pintype "bidirectional"))
    )
    (net (code "94") (name "/DAC_OUT_P23") (class "Default")
      (node (ref "J1") (pin "25") (pinfunction "25_25") (pintype "bidirectional"))
      (node (ref "J5") (pin "19") (pinfunction "19_19") (pintype "bidirectional"))
    )
    (net (code "95") (name "/DAC_OUT_P24") (class "Default")
      (node (ref "J1") (pin "26") (pinfunction "26_26") (pintype "bidirectional"))
      (node (ref "J5") (pin "22") (pinfunction "22_22") (pintype "bidirectional"))
    )
    (net (code "96") (name "/DAC_OUT_P25") (class "Default")
      (node (ref "J1") (pin "27") (pinfunction "27_27") (pintype "bidirectional"))
      (node (ref "J7") (pin "1") (pinfunction "1_1") (pintype "bidirectional"))
    )
    (net (code "97") (name "/DAC_OUT_P26") (class "Default")
      (node (ref "J1") (pin "28") (pinfunction "28_28") (pintype "bidirectional"))
      (node (ref "J7") (pin "4") (pinfunction "4_4") (pintype "bidirectional"))
    )
    (net (code "98") (name "/DAC_OUT_P27") (class "Default")
      (node (ref "J1") (pin "29") (pinfunction "29_29") (pintype "bidirectional"))
      (node (ref "J7") (pin "7") (pinfunction "7_7") (pintype "bidirectional"))
    )
    (net (code "99") (name "/DAC_OUT_P28") (class "Default")
      (node (ref "J1") (pin "30") (pinfunction "30_30") (pintype "bidirectional"))
      (node (ref "J7") (pin "10") (pinfunction "10_10") (pintype "bidirectional"))
    )
    (net (code "100") (name "/DAC_OUT_P29") (class "Default")
      (node (ref "J1") (pin "31") (pinfunction "31_31") (pintype "bidirectional"))
      (node (ref "J7") (pin "13") (pinfunction "13_13") (pintype "bidirectional"))
    )
    (net (code "101") (name "/DAC_OUT_P30") (class "Default")
      (node (ref "J1") (pin "32") (pinfunction "32_32") (pintype "bidirectional"))
      (node (ref "J7") (pin "16") (pinfunction "16_16") (pintype "bidirectional"))
    )
    (net (code "102") (name "/DAC_OUT_P31") (class "Default")
      (node (ref "J1") (pin "33") (pinfunction "33_33") (pintype "bidirectional"))
      (node (ref "J7") (pin "19") (pinfunction "19_19") (pintype "bidirectional"))
    )
    (net (code "103") (name "/DAC_OUT_P32") (class "Default")
      (node (ref "J1") (pin "34") (pinfunction "34_34") (pintype "bidirectional"))
      (node (ref "J7") (pin "22") (pinfunction "22_22") (pintype "bidirectional"))
    )
    (net (code "105") (name "/I2C_SCL") (class "Default")
      (node (ref "J2") (pin "12") (pinfunction "12_12") (pintype "bidirectional"))
    )
    (net (code "106") (name "/I2C_SDA") (class "Default")
      (node (ref "J2") (pin "11") (pinfunction "11_11") (pintype "bidirectional"))
    )
    (net (code "108") (name "/LED0") (class "Default")
      (node (ref "IC23") (pin "15") (pinfunction "QA_15") (pintype "tri_state"))
      (node (ref "R113") (pin "1") (pinfunction "1_1") (pintype "passive"))
    )
    (net (code "109") (name "/LED1") (class "Default")
      (node (ref "IC23") (pin "1") (pinfunction "QB_1") (pintype "tri_state"))
      (node (ref "R114") (pin "1") (pinfunction "1_1") (pintype "passive"))
    )
    (net (code "110") (name "/LED2") (class "Default")
      (node (ref "IC23") (pin "2") (pinfunction "QC_2") (pintype "tri_state"))
      (node (ref "R115") (pin "1") (pinfunction "1_1") (pintype "passive"))
    )
    (net (code "111") (name "/LED3") (class "Default")
      (node (ref "IC23") (pin "3") (pinfunction "QD_3") (pintype "tri_state"))
      (node (ref "R119") (pin "1") (pinfunction "1_1") (pintype "passive"))
    )
    (net (code "112") (name "/LED4") (class "Default")
      (node (ref "IC23") (pin "4") (pinfunction "QE_4") (pintype "tri_state"))
      (node (ref "R120") (pin "1") (pinfunction "1_1") (pintype "passive"))
    )
    (net (code "113") (name "/LED5") (class "Default")
      (node (ref "IC23") (pin "5") (pinfunction "QF_5") (pintype "tri_state"))
      (node (ref "R121") (pin "1") (pinfunction "1_1") (pintype "passive"))
    )
    (net (code "114") (name "/LED6") (class "Default")
      (node (ref "IC23") (pin "6") (pinfunction "QG_6") (pintype "tri_state"))
      (node (ref "R122") (pin "1") (pinfunction "1_1") (pintype "passive"))
    )
    (net (code "115") (name "/LED7") (class "Default")
      (node (ref "IC23") (pin "7") (pinfunction "QH_7") (pintype "tri_state"))
      (node (ref "R123") (pin "1") (pinfunction "1_1") (pintype "passive"))
    )
    (net (code "116") (name "/RESETn") (class "Default")
      (node (ref "IC19") (pin "2") (pinfunction "~{RST}_2") (pintype "output"))
    )
    (net (code "117") (name "/SCKI") (class "Default")
      (node (ref "IC23") (pin "11") (pinfunction "SRCLK_11") (pintype "input"))
      (node (ref "R117") (pin "2") (pinfunction "2_2") (pintype "passive"))
    )
    (net (code "118") (name "/SDI") (class "Default")
      (node (ref "IC23") (pin "14") (pinfunction "SER_14") (pintype "input"))
      (node (ref "R116") (pin "2") (pinfunction "2_2") (pintype "passive"))
    )
    (net (code "120") (name "/THERM_IO0") (class "Default")
      (node (ref "J2") (pin "13") (pinfunction "13_13") (pintype "bidirectional"))
    )
    (net (code "121") (name "/THERM_IO1") (class "Default")
      (node (ref "J2") (pin "14") (pinfunction "14_14") (pintype "bidirectional"))
    )
    (net (code "124") (name "/~{MR}") (class "Default")
      (node (ref "IC19") (pin "3") (pinfunction "~{MR}_3") (pintype "input"))
    )
    (net (code "125") (name "GND") (class "Default")
      (node (ref "C68") (pin "1") (pinfunction "1_1") (pintype "passive"))
      (node (ref "C71") (pin "1") (pinfunction "1_1") (pintype "passive"))
      (node (ref "C95") (pin "1") (pinfunction "1_1") (pintype "passive"))
      (node (ref "C96") (pin "1") (pinfunction "1_1") (pintype "passive"))
      (node (ref "CLIP27") (pin "1") (pinfunction "1_1") (pintype "passive"))
      (node (ref "CLIP28") (pin "1") (pinfunction "1_1") (pintype "passive"))
      (node (ref "CLIP29") (pin "1") (pinfunction "1_1") (pintype "passive"))
      (node (ref "CLIP30") (pin "1") (pinfunction "1_1") (pintype "passive"))
      (node (ref "CLIP31") (pin "1") (pinfunction "1_1") (pintype "passive"))
      (node (ref "CLIP32") (pin "1") (pinfunction "1_1") (pintype "passive"))
      (node (ref "CLIP33") (pin "1") (pinfunction "1_1") (pintype "passive"))
      (node (ref "CLIP34") (pin "1") (pinfunction "1_1") (pintype "passive"))
      (node (ref "CLIP35") (pin "1") (pinfunction "1_1") (pintype "passive"))
      (node (ref "CLIP36") (pin "1") (pinfunction "1_1") (pintype "passive"))
      (node (ref "CLIP37") (pin "1") (pinfunction "1_1") (pintype "passive"))
      (node (ref "CLIP38") (pin "1") (pinfunction "1_1") (pintype "passive"))
      (node (ref "CLIP39") (pin "1") (pinfunction "1_1") (pintype "passive"))
      (node (ref "CLIP40") (pin "1") (pinfunction "1_1") (pintype "passive"))
      (node (ref "CLIP41") (pin "1") (pinfunction "1_1") (pintype "passive"))
      (node (ref "CLIP42") (pin "1") (pinfunction "1_1") (pintype "passive"))
      (node (ref "CLIP43") (pin "1") (pinfunction "1_1") (pintype "passive"))
      (node (ref "CLIP44") (pin "1") (pinfunction "1_1") (pintype "passive"))
      (node (ref "CLIP45") (pin "1") (pinfunction "1_1") (pintype "passive"))
      (node (ref "CLIP46") (pin "1") (pinfunction "1_1") (pintype "passive"))
      (node (ref "CLIP47") (pin "1") (pinfunction "1_1") (pintype "passive"))
      (node (ref "CLIP48") (pin "1") (pinfunction "1_1") (pintype "passive"))
      (node (ref "CLIP49") (pin "1") (pinfunction "1_1") (pintype "passive"))
      (node (ref "CLIP50") (pin "1") (pinfunction "1_1") (pintype "passive"))
      (node (ref "CLIP51") (pin "1") (pinfunction "1_1") (pintype "passive"))
      (node (ref "CLIP52") (pin "1") (pinfunction "1_1") (pintype "passive"))
      (node (ref "IC19") (pin "1") (pinfunction "VSS_1") (pintype "power_in"))
      (node (ref "IC23") (pin "13") (pinfunction "~{OE}_13") (pintype "input"))
      (node (ref "IC23") (pin "8") (pinfunction "GND_8") (pintype "power_in"))
      (node (ref "J1") (pin "17") (pinfunction "17_17") (pintype "bidirectional"))
      (node (ref "J1") (pin "51") (pinfunction "51_51") (pintype "bidirectional"))
      (node (ref "J1") (pin "69") (pinfunction "69_69") (pintype "bidirectional"))
      (node (ref "J1") (pin "70") (pinfunction "70_70") (pintype "bidirectional"))
      (node (ref "J2") (pin "8") (pinfunction "8_8") (pintype "bidirectional"))
      (node (ref "J2") (pin "9") (pinfunction "9_9") (pintype "bidirectional"))
      (node (ref "J3") (pin "12") (pinfunction "12_12") (pintype "bidirectional"))
      (node (ref "J3") (pin "15") (pinfunction "15_15") (pintype "bidirectional"))
      (node (ref "J3") (pin "18") (pinfunction "18_18") (pintype "bidirectional"))
      (node (ref "J3") (pin "21") (pinfunction "21_21") (pintype "bidirectional"))
      (node (ref "J3") (pin "24") (pinfunction "24_24") (pintype "bidirectional"))
      (node (ref "J3") (pin "3") (pinfunction "3_3") (pintype "bidirectional"))
      (node (ref "J3") (pin "6") (pinfunction "6_6") (pintype "bidirectional"))
      (node (ref "J3") (pin "9") (pinfunction "9_9") (pintype "bidirectional"))
      (node (ref "J4") (pin "12") (pinfunction "12_12") (pintype "bidirectional"))
      (node (ref "J4") (pin "15") (pinfunction "15_15") (pintype "bidirectional"))
      (node (ref "J4") (pin "18") (pinfunction "18_18") (pintype "bidirectional"))
      (node (ref "J4") (pin "21") (pinfunction "21_21") (pintype "bidirectional"))
      (node (ref "J4") (pin "24") (pinfunction "24_24") (pintype "bidirectional"))
      (node (ref "J4") (pin "3") (pinfunction "3_3") (pintype "bidirectional"))
      (node (ref "J4") (pin "6") (pinfunction "6_6") (pintype "bidirectional"))
      (node (ref "J4") (pin "9") (pinfunction "9_9") (pintype "bidirectional"))
      (node (ref "J5") (pin "12") (pinfunction "12_12") (pintype "bidirectional"))
      (node (ref "J5") (pin "15") (pinfunction "15_15") (pintype "bidirectional"))
      (node (ref "J5") (pin "18") (pinfunction "18_18") (pintype "bidirectional"))
      (node (ref "J5") (pin "21") (pinfunction "21_21") (pintype "bidirectional"))
      (node (ref "J5") (pin "24") (pinfunction "24_24") (pintype "bidirectional"))
      (node (ref "J5") (pin "3") (pinfunction "3_3") (pintype "bidirectional"))
      (node (ref "J5") (pin "6") (pinfunction "6_6") (pintype "bidirectional"))
      (node (ref "J5") (pin "9") (pinfunction "9_9") (pintype "bidirectional"))
      (node (ref "J7") (pin "12") (pinfunction "12_12") (pintype "bidirectional"))
      (node (ref "J7") (pin "15") (pinfunction "15_15") (pintype "bidirectional"))
      (node (ref "J7") (pin "18") (pinfunction "18_18") (pintype "bidirectional"))
      (node (ref "J7") (pin "21") (pinfunction "21_21") (pintype "bidirectional"))
      (node (ref "J7") (pin "24") (pinfunction "24_24") (pintype "bidirectional"))
      (node (ref "J7") (pin "3") (pinfunction "3_3") (pintype "bidirectional"))
      (node (ref "J7") (pin "6") (pinfunction "6_6") (pintype "bidirectional"))
      (node (ref "J7") (pin "9") (pinfunction "9_9") (pintype "bidirectional"))
      (node (ref "LD4") (pin "1") (pinfunction "C_1") (pintype "passive"))
      (node (ref "LD4") (pin "3") (pinfunction "C_3") (pintype "passive"))
      (node (ref "LD4") (pin "5") (pinfunction "C_5") (pintype "passive"))
      (node (ref "LD4") (pin "7") (pinfunction "C_7") (pintype "passive"))
      (node (ref "LD5") (pin "1") (pinfunction "C_1") (pintype "passive"))
      (node (ref "LD5") (pin "3") (pinfunction "C_3") (pintype "passive"))
      (node (ref "LD5") (pin "5") (pinfunction "C_5") (pintype "passive"))
      (node (ref "LD5") (pin "7") (pinfunction "C_7") (pintype "passive"))
    )
    (net (code "126") (name "N13V0_SCSI") (class "Default")
      (node (ref "J1") (pin "52") (pinfunction "52_52") (pintype "bidirectional"))
      (node (ref "J3") (pin "26") (pinfunction "26_26") (pintype "bidirectional"))
      (node (ref "J4") (pin "26") (pinfunction "26_26") (pintype "bidirectional"))
      (node (ref "J5") (pin "26") (pinfunction "26_26") (pintype "bidirectional"))
      (node (ref "J7") (pin "26") (pinfunction "26_26") (pintype "bidirectional"))
    )
    (net (code "127") (name "Net-(B1-Pad1)") (class "Default")
      (node (ref "B1") (pin "1") (pinfunction "1_1") (pintype "bidirectional"))
      (node (ref "J2") (pin "3") (pinfunction "3_3") (pintype "bidirectional"))
      (node (ref "J2") (pin "4") (pinfunction "4_4") (pintype "bidirectional"))
    )
    (net (code "128") (name "Net-(B2-Pad1)") (class "Default")
      (node (ref "B2") (pin "1") (pinfunction "1_1") (pintype "bidirectional"))
      (node (ref "J2") (pin "5") (pinfunction "5_5") (pintype "bidirectional"))
      (node (ref "J2") (pin "6") (pinfunction "6_6") (pintype "bidirectional"))
    )
    (net (code "129") (name "Net-(C68-Pad2)") (class "Default")
      (node (ref "C68") (pin "2") (pinfunction "2_2") (pintype "passive"))
      (node (ref "R117") (pin "1") (pinfunction "1_1") (pintype "passive"))
    )
    (net (code "130") (name "Net-(C71-Pad2)") (class "Default")
      (node (ref "C71") (pin "2") (pinfunction "2_2") (pintype "passive"))
      (node (ref "R118") (pin "1") (pinfunction "1_1") (pintype "passive"))
    )
    (net (code "131") (name "Net-(C95-Pad2)") (class "Default")
      (node (ref "C95") (pin "2") (pinfunction "2_2") (pintype "passive"))
      (node (ref "R116") (pin "1") (pinfunction "1_1") (pintype "passive"))
    )
    (net (code "132") (name "Net-(J2-Pad1)") (class "Default")
      (node (ref "J2") (pin "1") (pinfunction "1_1") (pintype "bidirectional"))
      (node (ref "RT1") (pin "1") (pinfunction "1_1") (pintype "passive"))
    )
    (net (code "133") (name "Net-(J2-Pad2)") (class "Default")
      (node (ref "J2") (pin "2") (pinfunction "2_2") (pintype "bidirectional"))
      (node (ref "RT1") (pin "2") (pinfunction "2_2") (pintype "passive"))
    )
    (net (code "134") (name "Net-(LD4A-A)") (class "Default")
      (node (ref "LD4") (pin "2") (pinfunction "A_2") (pintype "passive"))
      (node (ref "R113") (pin "2") (pinfunction "2_2") (pintype "passive"))
    )
    (net (code "135") (name "Net-(LD4B-A)") (class "Default")
      (node (ref "LD4") (pin "4") (pinfunction "A_4") (pintype "passive"))
      (node (ref "R114") (pin "2") (pinfunction "2_2") (pintype "passive"))
    )
    (net (code "136") (name "Net-(LD4C-A)") (class "Default")
      (node (ref "LD4") (pin "6") (pinfunction "A_6") (pintype "passive"))
      (node (ref "R115") (pin "2") (pinfunction "2_2") (pintype "passive"))
    )
    (net (code "137") (name "Net-(LD4D-A)") (class "Default")
      (node (ref "LD4") (pin "8") (pinfunction "A_8") (pintype "passive"))
      (node (ref "R119") (pin "2") (pinfunction "2_2") (pintype "passive"))
    )
    (net (code "138") (name "Net-(LD5A-A)") (class "Default")
      (node (ref "LD5") (pin "2") (pinfunction "A_2") (pintype "passive"))
      (node (ref "R120") (pin "2") (pinfunction "2_2") (pintype "passive"))
    )
    (net (code "139") (name "Net-(LD5B-A)") (class "Default")
      (node (ref "LD5") (pin "4") (pinfunction "A_4") (pintype "passive"))
      (node (ref "R121") (pin "2") (pinfunction "2_2") (pintype "passive"))
    )
    (net (code "140") (name "Net-(LD5C-A)") (class "Default")
      (node (ref "LD5") (pin "6") (pinfunction "A_6") (pintype "passive"))
      (node (ref "R122") (pin "2") (pinfunction "2_2") (pintype "passive"))
    )
    (net (code "141") (name "Net-(LD5D-A)") (class "Default")
      (node (ref "LD5") (pin "8") (pinfunction "A_8") (pintype "passive"))
      (node (ref "R123") (pin "2") (pinfunction "2_2") (pintype "passive"))
    )
    (net (code "142") (name "P3V3") (class "Default")
      (node (ref "C96") (pin "2") (pinfunction "2_2") (pintype "passive"))
      (node (ref "IC19") (pin "4") (pinfunction "VCC_4") (pintype "power_in"))
      (node (ref "IC23") (pin "10") (pinfunction "~{SRCLR}_10") (pintype "input"))
      (node (ref "IC23") (pin "16") (pinfunction "VCC_16") (pintype "power_in"))
    )
    (net (code "143") (name "P3V3_MP") (class "Default")
      (node (ref "J2") (pin "10") (pinfunction "10_10") (pintype "bidirectional"))
    )
    (net (code "144") (name "P12V0") (class "Default")
      (node (ref "J2") (pin "7") (pinfunction "7_7") (pintype "bidirectional"))
    )
    (net (code "145") (name "P13V0_SCSI") (class "Default")
      (node (ref "J1") (pin "18") (pinfunction "18_18") (pintype "bidirectional"))
      (node (ref "J3") (pin "25") (pinfunction "25_25") (pintype "bidirectional"))
      (node (ref "J4") (pin "25") (pinfunction "25_25") (pintype "bidirectional"))
      (node (ref "J5") (pin "25") (pinfunction "25_25") (pintype "bidirectional"))
      (node (ref "J7") (pin "25") (pinfunction "25_25") (pintype "bidirectional"))
    )
    (net (code "146") (name "unconnected-(IC23-QH'-Pad9)") (class "Default")
      (node (ref "IC23") (pin "9") (pinfunction "QH'_9") (pintype "output"))
    )
  )
)
